# InputModule2.net
KiCad netlist of a schematic drawn in EAGLE
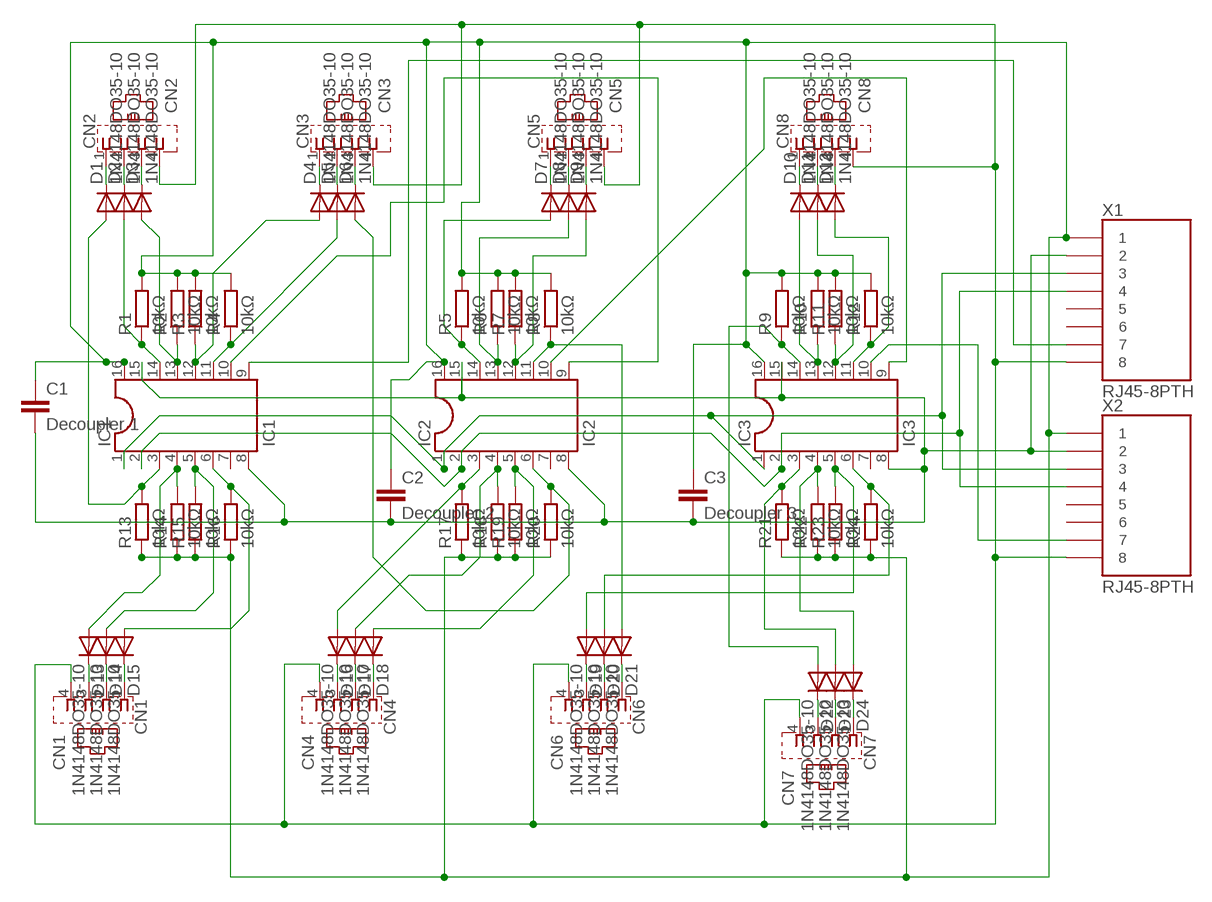
[diagram p0: schematic, sheet 1]

(export (version "E")
  (design (tool "Eeschema 10.0.6"))
  (components
    (comp (ref "C1")
      (value "Decoupler 1")
      (footprint "eagle-import:C5B2.5")
      (libsource (lib "eagle-import") (part "C5/2.5"))
    )
    (comp (ref "C2")
      (value "Decoupler 2")
      (footprint "eagle-import:C5B2.5")
      (libsource (lib "eagle-import") (part "C5/2.5"))
    )
    (comp (ref "C3")
      (value "Decoupler 3")
      (footprint "eagle-import:C5B2.5")
      (libsource (lib "eagle-import") (part "C5/2.5"))
    )
    (comp (ref "CN1")
      (value "CN1")
      (footprint "eagle-import:RJ116PC4")
      (libsource (lib "eagle-import") (part "RJ11-6PC4"))
    )
    (comp (ref "CN2")
      (value "CN2")
      (footprint "eagle-import:RJ116PC4")
      (libsource (lib "eagle-import") (part "RJ11-6PC4"))
    )
    (comp (ref "CN3")
      (value "CN3")
      (footprint "eagle-import:RJ116PC4")
      (libsource (lib "eagle-import") (part "RJ11-6PC4"))
    )
    (comp (ref "CN4")
      (value "CN4")
      (footprint "eagle-import:RJ116PC4")
      (libsource (lib "eagle-import") (part "RJ11-6PC4"))
    )
    (comp (ref "CN5")
      (value "CN5")
      (footprint "eagle-import:RJ116PC4")
      (libsource (lib "eagle-import") (part "RJ11-6PC4"))
    )
    (comp (ref "CN6")
      (value "CN6")
      (footprint "eagle-import:RJ116PC4")
      (libsource (lib "eagle-import") (part "RJ11-6PC4"))
    )
    (comp (ref "CN7")
      (value "CN7")
      (footprint "eagle-import:RJ116PC4")
      (libsource (lib "eagle-import") (part "RJ11-6PC4"))
    )
    (comp (ref "CN8")
      (value "CN8")
      (footprint "eagle-import:RJ116PC4")
      (libsource (lib "eagle-import") (part "RJ11-6PC4"))
    )
    (comp (ref "D1")
      (value "1N4148DO35-10")
      (footprint "eagle-import:DO35-10")
      (libsource (lib "eagle-import") (part "1N4148DO35-10"))
    )
    (comp (ref "D2")
      (value "1N4148DO35-10")
      (footprint "eagle-import:DO35-10")
      (libsource (lib "eagle-import") (part "1N4148DO35-10"))
    )
    (comp (ref "D3")
      (value "1N4148DO35-10")
      (footprint "eagle-import:DO35-10")
      (libsource (lib "eagle-import") (part "1N4148DO35-10"))
    )
    (comp (ref "D4")
      (value "1N4148DO35-10")
      (footprint "eagle-import:DO35-10")
      (libsource (lib "eagle-import") (part "1N4148DO35-10"))
    )
    (comp (ref "D5")
      (value "1N4148DO35-10")
      (footprint "eagle-import:DO35-10")
      (libsource (lib "eagle-import") (part "1N4148DO35-10"))
    )
    (comp (ref "D6")
      (value "1N4148DO35-10")
      (footprint "eagle-import:DO35-10")
      (libsource (lib "eagle-import") (part "1N4148DO35-10"))
    )
    (comp (ref "D7")
      (value "1N4148DO35-10")
      (footprint "eagle-import:DO35-10")
      (libsource (lib "eagle-import") (part "1N4148DO35-10"))
    )
    (comp (ref "D8")
      (value "1N4148DO35-10")
      (footprint "eagle-import:DO35-10")
      (libsource (lib "eagle-import") (part "1N4148DO35-10"))
    )
    (comp (ref "D9")
      (value "1N4148DO35-10")
      (footprint "eagle-import:DO35-10")
      (libsource (lib "eagle-import") (part "1N4148DO35-10"))
    )
    (comp (ref "D10")
      (value "1N4148DO35-10")
      (footprint "eagle-import:DO35-10")
      (libsource (lib "eagle-import") (part "1N4148DO35-10"))
    )
    (comp (ref "D11")
      (value "1N4148DO35-10")
      (footprint "eagle-import:DO35-10")
      (libsource (lib "eagle-import") (part "1N4148DO35-10"))
    )
    (comp (ref "D12")
      (value "1N4148DO35-10")
      (footprint "eagle-import:DO35-10")
      (libsource (lib "eagle-import") (part "1N4148DO35-10"))
    )
    (comp (ref "D13")
      (value "1N4148DO35-10")
      (footprint "eagle-import:DO35-10")
      (libsource (lib "eagle-import") (part "1N4148DO35-10"))
    )
    (comp (ref "D14")
      (value "1N4148DO35-10")
      (footprint "eagle-import:DO35-10")
      (libsource (lib "eagle-import") (part "1N4148DO35-10"))
    )
    (comp (ref "D15")
      (value "1N4148DO35-10")
      (footprint "eagle-import:DO35-10")
      (libsource (lib "eagle-import") (part "1N4148DO35-10"))
    )
    (comp (ref "D16")
      (value "1N4148DO35-10")
      (footprint "eagle-import:DO35-10")
      (libsource (lib "eagle-import") (part "1N4148DO35-10"))
    )
    (comp (ref "D17")
      (value "1N4148DO35-10")
      (footprint "eagle-import:DO35-10")
      (libsource (lib "eagle-import") (part "1N4148DO35-10"))
    )
    (comp (ref "D18")
      (value "1N4148DO35-10")
      (footprint "eagle-import:DO35-10")
      (libsource (lib "eagle-import") (part "1N4148DO35-10"))
    )
    (comp (ref "D19")
      (value "1N4148DO35-10")
      (footprint "eagle-import:DO35-10")
      (libsource (lib "eagle-import") (part "1N4148DO35-10"))
    )
    (comp (ref "D20")
      (value "1N4148DO35-10")
      (footprint "eagle-import:DO35-10")
      (libsource (lib "eagle-import") (part "1N4148DO35-10"))
    )
    (comp (ref "D21")
      (value "1N4148DO35-10")
      (footprint "eagle-import:DO35-10")
      (libsource (lib "eagle-import") (part "1N4148DO35-10"))
    )
    (comp (ref "D22")
      (value "1N4148DO35-10")
      (footprint "eagle-import:DO35-10")
      (libsource (lib "eagle-import") (part "1N4148DO35-10"))
    )
    (comp (ref "D23")
      (value "1N4148DO35-10")
      (footprint "eagle-import:DO35-10")
      (libsource (lib "eagle-import") (part "1N4148DO35-10"))
    )
    (comp (ref "D24")
      (value "1N4148DO35-10")
      (footprint "eagle-import:DO35-10")
      (libsource (lib "eagle-import") (part "1N4148DO35-10"))
    )
    (comp (ref "IC1")
      (value "IC1")
      (footprint "eagle-import:SOCKET-16")
      (libsource (lib "eagle-import") (part "DIL16S"))
    )
    (comp (ref "IC2")
      (value "IC2")
      (footprint "eagle-import:SOCKET-16")
      (libsource (lib "eagle-import") (part "DIL16S"))
    )
    (comp (ref "IC3")
      (value "IC3")
      (footprint "eagle-import:SOCKET-16")
      (libsource (lib "eagle-import") (part "DIL16S"))
    )
    (comp (ref "R1")
      (value "10kΩ")
      (footprint "eagle-import:0207_10")
      (libsource (lib "eagle-import") (part "R-EU_0207/10"))
    )
    (comp (ref "R2")
      (value "10kΩ")
      (footprint "eagle-import:0207_10")
      (libsource (lib "eagle-import") (part "R-EU_0207/10"))
    )
    (comp (ref "R3")
      (value "10kΩ")
      (footprint "eagle-import:0207_10")
      (libsource (lib "eagle-import") (part "R-EU_0207/10"))
    )
    (comp (ref "R4")
      (value "10kΩ")
      (footprint "eagle-import:0207_10")
      (libsource (lib "eagle-import") (part "R-EU_0207/10"))
    )
    (comp (ref "R5")
      (value "10kΩ")
      (footprint "eagle-import:0207_10")
      (libsource (lib "eagle-import") (part "R-EU_0207/10"))
    )
    (comp (ref "R6")
      (value "10kΩ")
      (footprint "eagle-import:0207_10")
      (libsource (lib "eagle-import") (part "R-EU_0207/10"))
    )
    (comp (ref "R7")
      (value "10kΩ")
      (footprint "eagle-import:0207_10")
      (libsource (lib "eagle-import") (part "R-EU_0207/10"))
    )
    (comp (ref "R8")
      (value "10kΩ")
      (footprint "eagle-import:0207_10")
      (libsource (lib "eagle-import") (part "R-EU_0207/10"))
    )
    (comp (ref "R9")
      (value "10kΩ")
      (footprint "eagle-import:0207_10")
      (libsource (lib "eagle-import") (part "R-EU_0207/10"))
    )
    (comp (ref "R10")
      (value "10kΩ")
      (footprint "eagle-import:0207_10")
      (libsource (lib "eagle-import") (part "R-EU_0207/10"))
    )
    (comp (ref "R11")
      (value "10kΩ")
      (footprint "eagle-import:0207_10")
      (libsource (lib "eagle-import") (part "R-EU_0207/10"))
    )
    (comp (ref "R12")
      (value "10kΩ")
      (footprint "eagle-import:0207_10")
      (libsource (lib "eagle-import") (part "R-EU_0207/10"))
    )
    (comp (ref "R13")
      (value "10kΩ")
      (footprint "eagle-import:0207_10")
      (libsource (lib "eagle-import") (part "R-EU_0207/10"))
    )
    (comp (ref "R14")
      (value "10kΩ")
      (footprint "eagle-import:0207_10")
      (libsource (lib "eagle-import") (part "R-EU_0207/10"))
    )
    (comp (ref "R15")
      (value "10kΩ")
      (footprint "eagle-import:0207_10")
      (libsource (lib "eagle-import") (part "R-EU_0207/10"))
    )
    (comp (ref "R16")
      (value "10kΩ")
      (footprint "eagle-import:0207_10")
      (libsource (lib "eagle-import") (part "R-EU_0207/10"))
    )
    (comp (ref "R17")
      (value "10kΩ")
      (footprint "eagle-import:0207_10")
      (libsource (lib "eagle-import") (part "R-EU_0207/10"))
    )
    (comp (ref "R18")
      (value "10kΩ")
      (footprint "eagle-import:0207_10")
      (libsource (lib "eagle-import") (part "R-EU_0207/10"))
    )
    (comp (ref "R19")
      (value "10kΩ")
      (footprint "eagle-import:0207_10")
      (libsource (lib "eagle-import") (part "R-EU_0207/10"))
    )
    (comp (ref "R20")
      (value "10kΩ")
      (footprint "eagle-import:0207_10")
      (libsource (lib "eagle-import") (part "R-EU_0207/10"))
    )
    (comp (ref "R21")
      (value "10kΩ")
      (footprint "eagle-import:0207_10")
      (libsource (lib "eagle-import") (part "R-EU_0207/10"))
    )
    (comp (ref "R22")
      (value "10kΩ")
      (footprint "eagle-import:0207_10")
      (libsource (lib "eagle-import") (part "R-EU_0207/10"))
    )
    (comp (ref "R23")
      (value "10kΩ")
      (footprint "eagle-import:0207_10")
      (libsource (lib "eagle-import") (part "R-EU_0207/10"))
    )
    (comp (ref "R24")
      (value "10kΩ")
      (footprint "eagle-import:0207_10")
      (libsource (lib "eagle-import") (part "R-EU_0207/10"))
    )
    (comp (ref "X1")
      (value "RJ45-8PTH")
      (footprint "eagle-import:RJ45-8")
      (libsource (lib "eagle-import") (part "RJ45-8PTH"))
    )
    (comp (ref "X2")
      (value "RJ45-8PTH")
      (footprint "eagle-import:RJ45-8")
      (libsource (lib "eagle-import") (part "RJ45-8PTH"))
    )
  )
  (nets
    (net (code "1") (name "Net-(C1-Pad1)") (class "Default")
      (node (ref "C1") (pin "1") (pinfunction "1_1") (pintype "passive"))
      (node (ref "C2") (pin "1") (pinfunction "1_1") (pintype "passive"))
      (node (ref "C3") (pin "1") (pinfunction "1_1") (pintype "passive"))
      (node (ref "IC1") (pin "16") (pinfunction "16_16") (pintype "passive"))
      (node (ref "IC2") (pin "16") (pinfunction "16_16") (pintype "passive"))
      (node (ref "IC3") (pin "16") (pinfunction "16_16") (pintype "passive"))
      (node (ref "R1") (pin "2") (pinfunction "2_2") (pintype "passive"))
      (node (ref "R10") (pin "2") (pinfunction "2_2") (pintype "passive"))
      (node (ref "R11") (pin "2") (pinfunction "2_2") (pintype "passive"))
      (node (ref "R12") (pin "2") (pinfunction "2_2") (pintype "passive"))
      (node (ref "R13") (pin "1") (pinfunction "1_1") (pintype "passive"))
      (node (ref "R14") (pin "1") (pinfunction "1_1") (pintype "passive"))
      (node (ref "R15") (pin "1") (pinfunction "1_1") (pintype "passive"))
      (node (ref "R16") (pin "1") (pinfunction "1_1") (pintype "passive"))
      (node (ref "R17") (pin "1") (pinfunction "1_1") (pintype "passive"))
      (node (ref "R18") (pin "1") (pinfunction "1_1") (pintype "passive"))
      (node (ref "R19") (pin "1") (pinfunction "1_1") (pintype "passive"))
      (node (ref "R2") (pin "2") (pinfunction "2_2") (pintype "passive"))
      (node (ref "R20") (pin "1") (pinfunction "1_1") (pintype "passive"))
      (node (ref "R21") (pin "1") (pinfunction "1_1") (pintype "passive"))
      (node (ref "R22") (pin "1") (pinfunction "1_1") (pintype "passive"))
      (node (ref "R23") (pin "1") (pinfunction "1_1") (pintype "passive"))
      (node (ref "R24") (pin "1") (pinfunction "1_1") (pintype "passive"))
      (node (ref "R3") (pin "2") (pinfunction "2_2") (pintype "passive"))
      (node (ref "R4") (pin "2") (pinfunction "2_2") (pintype "passive"))
      (node (ref "R5") (pin "2") (pinfunction "2_2") (pintype "passive"))
      (node (ref "R6") (pin "2") (pinfunction "2_2") (pintype "passive"))
      (node (ref "R7") (pin "2") (pinfunction "2_2") (pintype "passive"))
      (node (ref "R8") (pin "2") (pinfunction "2_2") (pintype "passive"))
      (node (ref "R9") (pin "2") (pinfunction "2_2") (pintype "passive"))
      (node (ref "X1") (pin "1") (pinfunction "1_1") (pintype "bidirectional"))
      (node (ref "X2") (pin "1") (pinfunction "1_1") (pintype "bidirectional"))
    )
    (net (code "2") (name "Net-(C1-Pad2)") (class "Default")
      (node (ref "C1") (pin "2") (pinfunction "2_2") (pintype "passive"))
      (node (ref "C2") (pin "2") (pinfunction "2_2") (pintype "passive"))
      (node (ref "C3") (pin "2") (pinfunction "2_2") (pintype "passive"))
      (node (ref "IC1") (pin "15") (pinfunction "15_15") (pintype "passive"))
      (node (ref "IC1") (pin "8") (pinfunction "8_8") (pintype "passive"))
      (node (ref "IC2") (pin "15") (pinfunction "15_15") (pintype "passive"))
      (node (ref "IC2") (pin "8") (pinfunction "8_8") (pintype "passive"))
      (node (ref "IC3") (pin "15") (pinfunction "15_15") (pintype "passive"))
      (node (ref "IC3") (pin "8") (pinfunction "8_8") (pintype "passive"))
      (node (ref "X1") (pin "2") (pinfunction "2_2") (pintype "bidirectional"))
      (node (ref "X2") (pin "2") (pinfunction "2_2") (pintype "bidirectional"))
    )
    (net (code "3") (name "Net-(CN1-Pad1)") (class "Default")
      (node (ref "CN1") (pin "1") (pinfunction "1_1") (pintype "passive"))
      (node (ref "D15") (pin "C") (pinfunction "C_C") (pintype "passive"))
    )
    (net (code "4") (name "Net-(CN1-Pad2)") (class "Default")
      (node (ref "CN1") (pin "2") (pinfunction "2_2") (pintype "passive"))
      (node (ref "D14") (pin "C") (pinfunction "C_C") (pintype "passive"))
    )
    (net (code "5") (name "Net-(CN1-Pad3)") (class "Default")
      (node (ref "CN1") (pin "3") (pinfunction "3_3") (pintype "passive"))
      (node (ref "D13") (pin "C") (pinfunction "C_C") (pintype "passive"))
    )
    (net (code "6") (name "Net-(CN1-Pad4)") (class "Default")
      (node (ref "CN1") (pin "4") (pinfunction "4_4") (pintype "passive"))
      (node (ref "CN2") (pin "4") (pinfunction "4_4") (pintype "passive"))
      (node (ref "CN3") (pin "4") (pinfunction "4_4") (pintype "passive"))
      (node (ref "CN4") (pin "4") (pinfunction "4_4") (pintype "passive"))
      (node (ref "CN5") (pin "4") (pinfunction "4_4") (pintype "passive"))
      (node (ref "CN6") (pin "4") (pinfunction "4_4") (pintype "passive"))
      (node (ref "CN7") (pin "4") (pinfunction "4_4") (pintype "passive"))
      (node (ref "CN8") (pin "4") (pinfunction "4_4") (pintype "passive"))
      (node (ref "X1") (pin "8") (pinfunction "8_8") (pintype "bidirectional"))
      (node (ref "X2") (pin "8") (pinfunction "8_8") (pintype "bidirectional"))
    )
    (net (code "7") (name "Net-(CN2-Pad1)") (class "Default")
      (node (ref "CN2") (pin "1") (pinfunction "1_1") (pintype "passive"))
      (node (ref "D1") (pin "C") (pinfunction "C_C") (pintype "passive"))
    )
    (net (code "8") (name "Net-(CN2-Pad2)") (class "Default")
      (node (ref "CN2") (pin "2") (pinfunction "2_2") (pintype "passive"))
      (node (ref "D2") (pin "C") (pinfunction "C_C") (pintype "passive"))
    )
    (net (code "9") (name "Net-(CN2-Pad3)") (class "Default")
      (node (ref "CN2") (pin "3") (pinfunction "3_3") (pintype "passive"))
      (node (ref "D3") (pin "C") (pinfunction "C_C") (pintype "passive"))
    )
    (net (code "10") (name "Net-(CN3-Pad1)") (class "Default")
      (node (ref "CN3") (pin "1") (pinfunction "1_1") (pintype "passive"))
      (node (ref "D4") (pin "C") (pinfunction "C_C") (pintype "passive"))
    )
    (net (code "11") (name "Net-(CN3-Pad2)") (class "Default")
      (node (ref "CN3") (pin "2") (pinfunction "2_2") (pintype "passive"))
      (node (ref "D5") (pin "C") (pinfunction "C_C") (pintype "passive"))
    )
    (net (code "12") (name "Net-(CN3-Pad3)") (class "Default")
      (node (ref "CN3") (pin "3") (pinfunction "3_3") (pintype "passive"))
      (node (ref "D6") (pin "C") (pinfunction "C_C") (pintype "passive"))
    )
    (net (code "13") (name "Net-(CN4-Pad1)") (class "Default")
      (node (ref "CN4") (pin "1") (pinfunction "1_1") (pintype "passive"))
      (node (ref "D18") (pin "C") (pinfunction "C_C") (pintype "passive"))
    )
    (net (code "14") (name "Net-(CN4-Pad2)") (class "Default")
      (node (ref "CN4") (pin "2") (pinfunction "2_2") (pintype "passive"))
      (node (ref "D17") (pin "C") (pinfunction "C_C") (pintype "passive"))
    )
    (net (code "15") (name "Net-(CN4-Pad3)") (class "Default")
      (node (ref "CN4") (pin "3") (pinfunction "3_3") (pintype "passive"))
      (node (ref "D16") (pin "C") (pinfunction "C_C") (pintype "passive"))
    )
    (net (code "16") (name "Net-(CN5-Pad1)") (class "Default")
      (node (ref "CN5") (pin "1") (pinfunction "1_1") (pintype "passive"))
      (node (ref "D7") (pin "C") (pinfunction "C_C") (pintype "passive"))
    )
    (net (code "17") (name "Net-(CN5-Pad2)") (class "Default")
      (node (ref "CN5") (pin "2") (pinfunction "2_2") (pintype "passive"))
      (node (ref "D8") (pin "C") (pinfunction "C_C") (pintype "passive"))
    )
    (net (code "18") (name "Net-(CN5-Pad3)") (class "Default")
      (node (ref "CN5") (pin "3") (pinfunction "3_3") (pintype "passive"))
      (node (ref "D9") (pin "C") (pinfunction "C_C") (pintype "passive"))
    )
    (net (code "19") (name "Net-(CN6-Pad1)") (class "Default")
      (node (ref "CN6") (pin "1") (pinfunction "1_1") (pintype "passive"))
      (node (ref "D21") (pin "C") (pinfunction "C_C") (pintype "passive"))
    )
    (net (code "20") (name "Net-(CN6-Pad2)") (class "Default")
      (node (ref "CN6") (pin "2") (pinfunction "2_2") (pintype "passive"))
      (node (ref "D20") (pin "C") (pinfunction "C_C") (pintype "passive"))
    )
    (net (code "21") (name "Net-(CN6-Pad3)") (class "Default")
      (node (ref "CN6") (pin "3") (pinfunction "3_3") (pintype "passive"))
      (node (ref "D19") (pin "C") (pinfunction "C_C") (pintype "passive"))
    )
    (net (code "22") (name "Net-(CN7-Pad1)") (class "Default")
      (node (ref "CN7") (pin "1") (pinfunction "1_1") (pintype "passive"))
      (node (ref "D24") (pin "C") (pinfunction "C_C") (pintype "passive"))
    )
    (net (code "23") (name "Net-(CN7-Pad2)") (class "Default")
      (node (ref "CN7") (pin "2") (pinfunction "2_2") (pintype "passive"))
      (node (ref "D23") (pin "C") (pinfunction "C_C") (pintype "passive"))
    )
    (net (code "24") (name "Net-(CN7-Pad3)") (class "Default")
      (node (ref "CN7") (pin "3") (pinfunction "3_3") (pintype "passive"))
      (node (ref "D22") (pin "C") (pinfunction "C_C") (pintype "passive"))
    )
    (net (code "25") (name "Net-(CN8-Pad1)") (class "Default")
      (node (ref "CN8") (pin "1") (pinfunction "1_1") (pintype "passive"))
      (node (ref "D10") (pin "C") (pinfunction "C_C") (pintype "passive"))
    )
    (net (code "26") (name "Net-(CN8-Pad2)") (class "Default")
      (node (ref "CN8") (pin "2") (pinfunction "2_2") (pintype "passive"))
      (node (ref "D11") (pin "C") (pinfunction "C_C") (pintype "passive"))
    )
    (net (code "27") (name "Net-(CN8-Pad3)") (class "Default")
      (node (ref "CN8") (pin "3") (pinfunction "3_3") (pintype "passive"))
      (node (ref "D12") (pin "C") (pinfunction "C_C") (pintype "passive"))
    )
    (net (code "28") (name "Net-(D1-PadA)") (class "Default")
      (node (ref "D1") (pin "A") (pinfunction "A_A") (pintype "passive"))
      (node (ref "IC1") (pin "3") (pinfunction "3_3") (pintype "passive"))
      (node (ref "R13") (pin "2") (pinfunction "2_2") (pintype "passive"))
    )
    (net (code "29") (name "Net-(D2-PadA)") (class "Default")
      (node (ref "D2") (pin "A") (pinfunction "A_A") (pintype "passive"))
      (node (ref "IC1") (pin "14") (pinfunction "14_14") (pintype "passive"))
      (node (ref "R1") (pin "1") (pinfunction "1_1") (pintype "passive"))
    )
    (net (code "30") (name "Net-(D3-PadA)") (class "Default")
      (node (ref "D3") (pin "A") (pinfunction "A_A") (pintype "passive"))
      (node (ref "IC1") (pin "13") (pinfunction "13_13") (pintype "passive"))
      (node (ref "R2") (pin "1") (pinfunction "1_1") (pintype "passive"))
    )
    (net (code "31") (name "Net-(D4-PadA)") (class "Default")
      (node (ref "D4") (pin "A") (pinfunction "A_A") (pintype "passive"))
      (node (ref "IC1") (pin "12") (pinfunction "12_12") (pintype "passive"))
      (node (ref "R3") (pin "1") (pinfunction "1_1") (pintype "passive"))
    )
    (net (code "32") (name "Net-(D5-PadA)") (class "Default")
      (node (ref "D5") (pin "A") (pinfunction "A_A") (pintype "passive"))
      (node (ref "IC1") (pin "11") (pinfunction "11_11") (pintype "passive"))
      (node (ref "R4") (pin "1") (pinfunction "1_1") (pintype "passive"))
    )
    (net (code "33") (name "Net-(D6-PadA)") (class "Default")
      (node (ref "D6") (pin "A") (pinfunction "A_A") (pintype "passive"))
      (node (ref "IC2") (pin "6") (pinfunction "6_6") (pintype "passive"))
      (node (ref "R20") (pin "2") (pinfunction "2_2") (pintype "passive"))
    )
    (net (code "34") (name "Net-(D7-PadA)") (class "Default")
      (node (ref "D7") (pin "A") (pinfunction "A_A") (pintype "passive"))
      (node (ref "IC2") (pin "14") (pinfunction "14_14") (pintype "passive"))
      (node (ref "R5") (pin "1") (pinfunction "1_1") (pintype "passive"))
    )
    (net (code "35") (name "Net-(D8-PadA)") (class "Default")
      (node (ref "D8") (pin "A") (pinfunction "A_A") (pintype "passive"))
      (node (ref "IC2") (pin "13") (pinfunction "13_13") (pintype "passive"))
      (node (ref "R6") (pin "1") (pinfunction "1_1") (pintype "passive"))
    )
    (net (code "36") (name "Net-(D9-PadA)") (class "Default")
      (node (ref "D9") (pin "A") (pinfunction "A_A") (pintype "passive"))
      (node (ref "IC2") (pin "12") (pinfunction "12_12") (pintype "passive"))
      (node (ref "R7") (pin "1") (pinfunction "1_1") (pintype "passive"))
    )
    (net (code "37") (name "Net-(D10-PadA)") (class "Default")
      (node (ref "D10") (pin "A") (pinfunction "A_A") (pintype "passive"))
      (node (ref "IC3") (pin "13") (pinfunction "13_13") (pintype "passive"))
      (node (ref "R10") (pin "1") (pinfunction "1_1") (pintype "passive"))
    )
    (net (code "38") (name "Net-(D11-PadA)") (class "Default")
      (node (ref "D11") (pin "A") (pinfunction "A_A") (pintype "passive"))
      (node (ref "IC3") (pin "12") (pinfunction "12_12") (pintype "passive"))
      (node (ref "R11") (pin "1") (pinfunction "1_1") (pintype "passive"))
    )
    (net (code "39") (name "Net-(D12-PadA)") (class "Default")
      (node (ref "D12") (pin "A") (pinfunction "A_A") (pintype "passive"))
      (node (ref "IC3") (pin "11") (pinfunction "11_11") (pintype "passive"))
      (node (ref "R12") (pin "1") (pinfunction "1_1") (pintype "passive"))
    )
    (net (code "40") (name "Net-(D13-PadA)") (class "Default")
      (node (ref "D13") (pin "A") (pinfunction "A_A") (pintype "passive"))
      (node (ref "IC1") (pin "4") (pinfunction "4_4") (pintype "passive"))
      (node (ref "R14") (pin "2") (pinfunction "2_2") (pintype "passive"))
    )
    (net (code "41") (name "Net-(D14-PadA)") (class "Default")
      (node (ref "D14") (pin "A") (pinfunction "A_A") (pintype "passive"))
      (node (ref "IC1") (pin "5") (pinfunction "5_5") (pintype "passive"))
      (node (ref "R15") (pin "2") (pinfunction "2_2") (pintype "passive"))
    )
    (net (code "42") (name "Net-(D15-PadA)") (class "Default")
      (node (ref "D15") (pin "A") (pinfunction "A_A") (pintype "passive"))
      (node (ref "IC1") (pin "6") (pinfunction "6_6") (pintype "passive"))
      (node (ref "R16") (pin "2") (pinfunction "2_2") (pintype "passive"))
    )
    (net (code "43") (name "Net-(D16-PadA)") (class "Default")
      (node (ref "D16") (pin "A") (pinfunction "A_A") (pintype "passive"))
      (node (ref "IC2") (pin "3") (pinfunction "3_3") (pintype "passive"))
      (node (ref "R17") (pin "2") (pinfunction "2_2") (pintype "passive"))
    )
    (net (code "44") (name "Net-(D17-PadA)") (class "Default")
      (node (ref "D17") (pin "A") (pinfunction "A_A") (pintype "passive"))
      (node (ref "IC2") (pin "4") (pinfunction "4_4") (pintype "passive"))
      (node (ref "R18") (pin "2") (pinfunction "2_2") (pintype "passive"))
    )
    (net (code "45") (name "Net-(D18-PadA)") (class "Default")
      (node (ref "D18") (pin "A") (pinfunction "A_A") (pintype "passive"))
      (node (ref "IC2") (pin "5") (pinfunction "5_5") (pintype "passive"))
      (node (ref "R19") (pin "2") (pinfunction "2_2") (pintype "passive"))
    )
    (net (code "46") (name "Net-(D19-PadA)") (class "Default")
      (node (ref "D19") (pin "A") (pinfunction "A_A") (pintype "passive"))
      (node (ref "IC3") (pin "5") (pinfunction "5_5") (pintype "passive"))
      (node (ref "R23") (pin "2") (pinfunction "2_2") (pintype "passive"))
    )
    (net (code "47") (name "Net-(D20-PadA)") (class "Default")
      (node (ref "D20") (pin "A") (pinfunction "A_A") (pintype "passive"))
      (node (ref "IC3") (pin "6") (pinfunction "6_6") (pintype "passive"))
      (node (ref "R24") (pin "2") (pinfunction "2_2") (pintype "passive"))
    )
    (net (code "48") (name "Net-(D21-PadA)") (class "Default")
      (node (ref "D21") (pin "A") (pinfunction "A_A") (pintype "passive"))
      (node (ref "IC2") (pin "11") (pinfunction "11_11") (pintype "passive"))
      (node (ref "R8") (pin "1") (pinfunction "1_1") (pintype "passive"))
    )
    (net (code "49") (name "Net-(D22-PadA)") (class "Default")
      (node (ref "D22") (pin "A") (pinfunction "A_A") (pintype "passive"))
      (node (ref "IC3") (pin "14") (pinfunction "14_14") (pintype "passive"))
      (node (ref "R9") (pin "1") (pinfunction "1_1") (pintype "passive"))
    )
    (net (code "50") (name "Net-(D23-PadA)") (class "Default")
      (node (ref "D23") (pin "A") (pinfunction "A_A") (pintype "passive"))
      (node (ref "IC3") (pin "3") (pinfunction "3_3") (pintype "passive"))
      (node (ref "R21") (pin "2") (pinfunction "2_2") (pintype "passive"))
    )
    (net (code "51") (name "Net-(D24-PadA)") (class "Default")
      (node (ref "D24") (pin "A") (pinfunction "A_A") (pintype "passive"))
      (node (ref "IC3") (pin "4") (pinfunction "4_4") (pintype "passive"))
      (node (ref "R22") (pin "2") (pinfunction "2_2") (pintype "passive"))
    )
    (net (code "52") (name "Net-(IC1-Pad1)") (class "Default")
      (node (ref "IC1") (pin "1") (pinfunction "1_1") (pintype "passive"))
      (node (ref "IC2") (pin "1") (pinfunction "1_1") (pintype "passive"))
      (node (ref "IC3") (pin "1") (pinfunction "1_1") (pintype "passive"))
      (node (ref "X1") (pin "3") (pinfunction "3_3") (pintype "bidirectional"))
      (node (ref "X2") (pin "3") (pinfunction "3_3") (pintype "bidirectional"))
    )
    (net (code "53") (name "Net-(IC1-Pad2)") (class "Default")
      (node (ref "IC1") (pin "2") (pinfunction "2_2") (pintype "passive"))
      (node (ref "IC2") (pin "2") (pinfunction "2_2") (pintype "passive"))
      (node (ref "IC3") (pin "2") (pinfunction "2_2") (pintype "passive"))
      (node (ref "X1") (pin "4") (pinfunction "4_4") (pintype "bidirectional"))
      (node (ref "X2") (pin "4") (pinfunction "4_4") (pintype "bidirectional"))
    )
    (net (code "54") (name "Net-(IC1-Pad9)") (class "Default")
      (node (ref "IC1") (pin "9") (pinfunction "9_9") (pintype "passive"))
      (node (ref "X1") (pin "7") (pinfunction "7_7") (pintype "bidirectional"))
    )
    (net (code "55") (name "Net-(IC1-Pad10)") (class "Default")
      (node (ref "IC1") (pin "10") (pinfunction "10_10") (pintype "passive"))
      (node (ref "IC2") (pin "9") (pinfunction "9_9") (pintype "passive"))
    )
    (net (code "56") (name "Net-(IC2-Pad10)") (class "Default")
      (node (ref "IC2") (pin "10") (pinfunction "10_10") (pintype "passive"))
      (node (ref "IC3") (pin "9") (pinfunction "9_9") (pintype "passive"))
    )
    (net (code "57") (name "Net-(IC3-Pad10)") (class "Default")
      (node (ref "IC3") (pin "10") (pinfunction "10_10") (pintype "passive"))
      (node (ref "X2") (pin "7") (pinfunction "7_7") (pintype "bidirectional"))
    )
    (net (code "58") (name "unconnected-(IC1-Pad7)") (class "Default")
      (node (ref "IC1") (pin "7") (pinfunction "7_7") (pintype "passive"))
    )
    (net (code "59") (name "unconnected-(IC2-Pad7)") (class "Default")
      (node (ref "IC2") (pin "7") (pinfunction "7_7") (pintype "passive"))
    )
    (net (code "60") (name "unconnected-(IC3-Pad7)") (class "Default")
      (node (ref "IC3") (pin "7") (pinfunction "7_7") (pintype "passive"))
    )
    (net (code "61") (name "unconnected-(X1-Pad5)") (class "Default")
      (node (ref "X1") (pin "5") (pinfunction "5_5") (pintype "bidirectional"))
    )
    (net (code "62") (name "unconnected-(X1-Pad6)") (class "Default")
      (node (ref "X1") (pin "6") (pinfunction "6_6") (pintype "bidirectional"))
    )
    (net (code "63") (name "unconnected-(X2-Pad5)") (class "Default")
      (node (ref "X2") (pin "5") (pinfunction "5_5") (pintype "bidirectional"))
    )
    (net (code "64") (name "unconnected-(X2-Pad6)") (class "Default")
      (node (ref "X2") (pin "6") (pinfunction "6_6") (pintype "bidirectional"))
    )
  )
)
